# T17_Schematic_The_Useless_Box.net
KiCad netlist of a schematic drawn in EAGLE
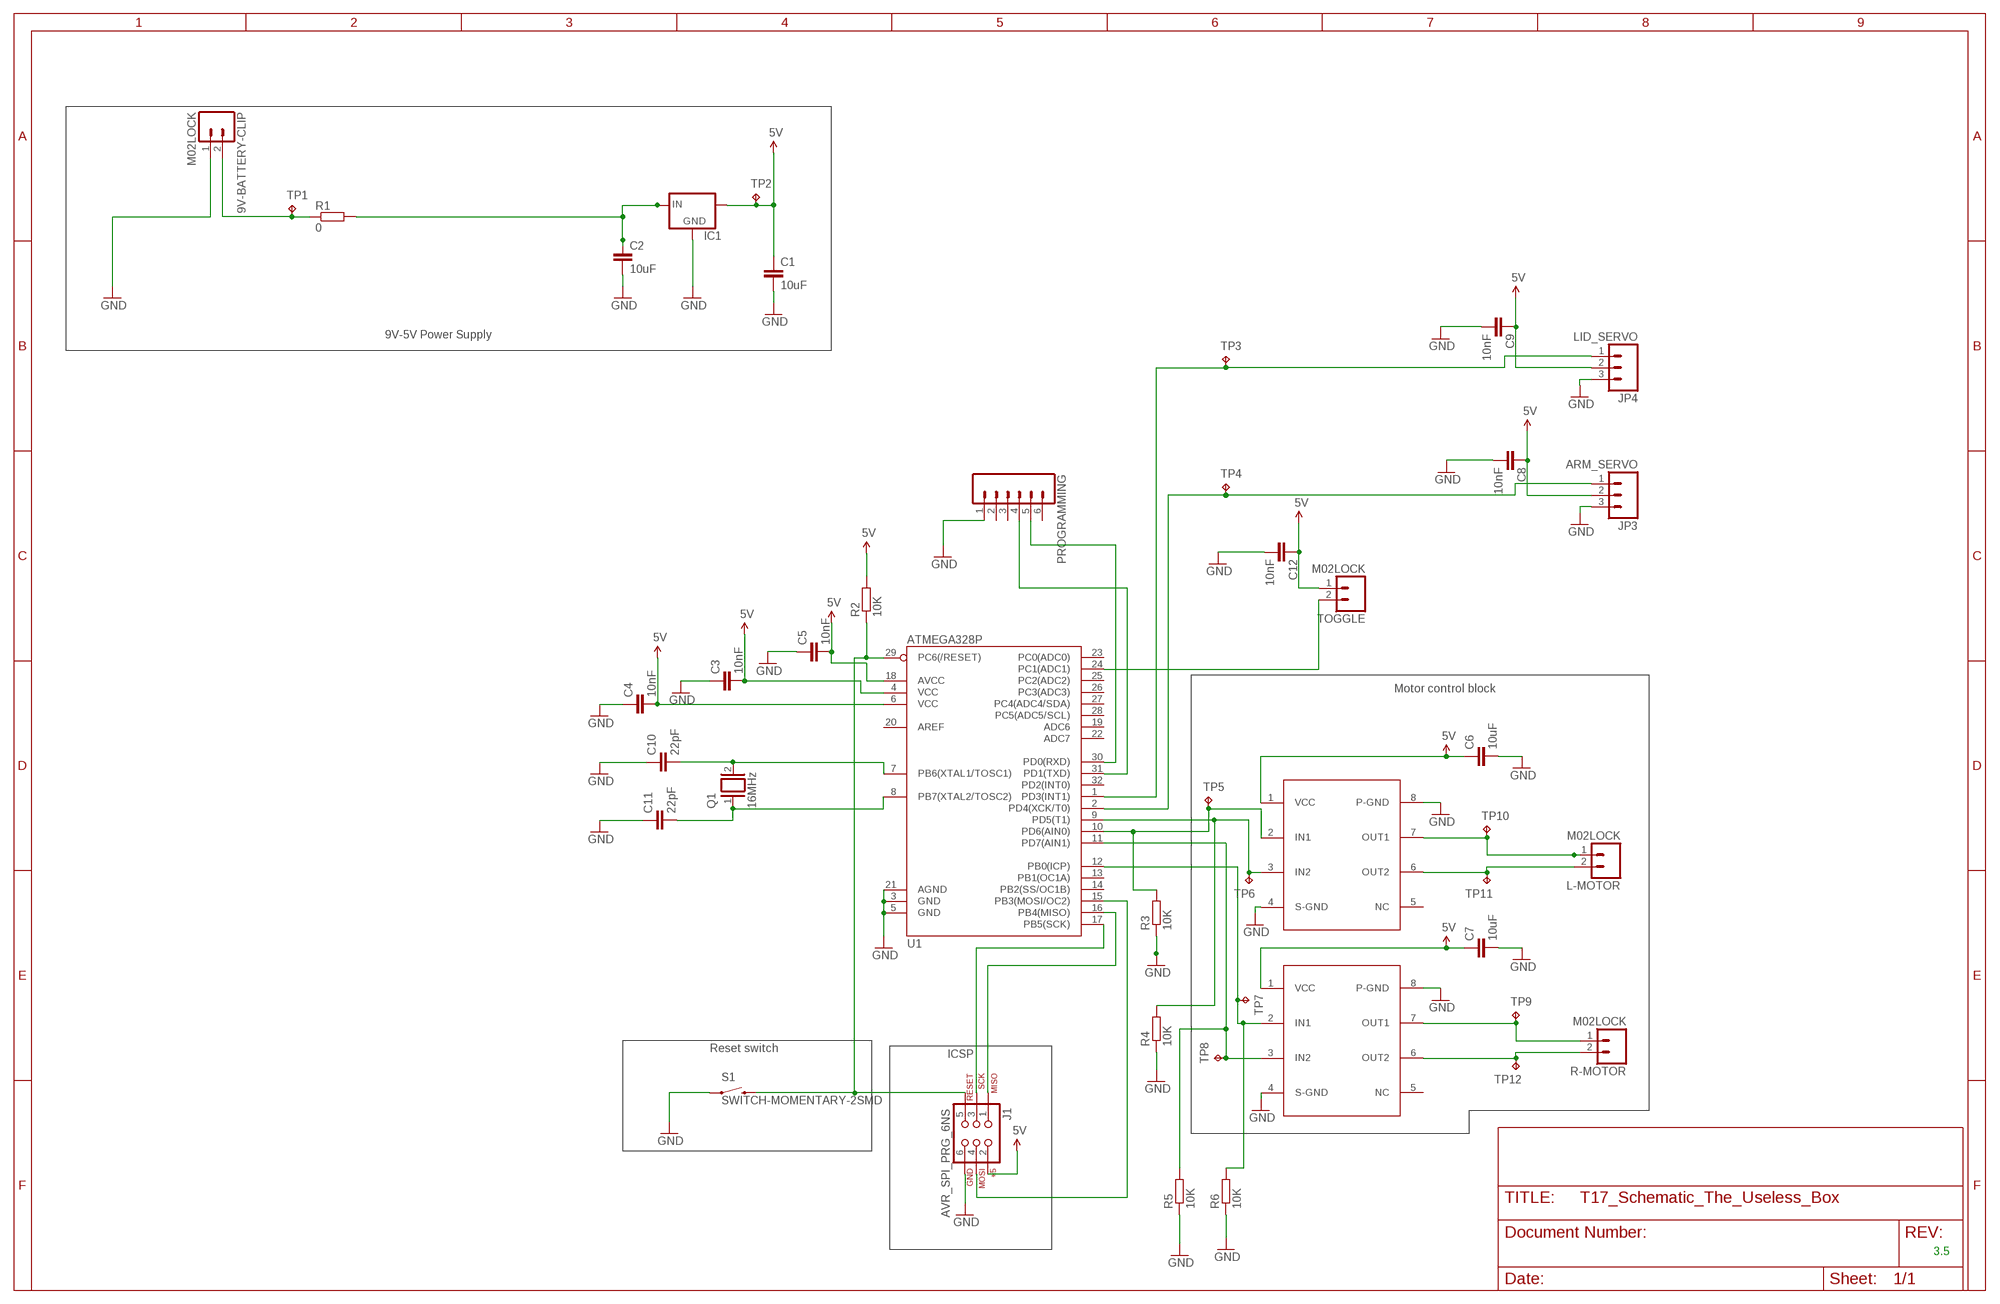
[diagram p0: schematic, sheet 1]

(export (version "E")
  (design (tool "Eeschema 10.0.6"))
  (components
    (comp (ref "9V-BATTERY-CLIP")
      (value "M02LOCK")
      (footprint "eagle-import:1X02_LOCK")
      (libsource (lib "eagle-import") (part "M02LOCK"))
    )
    (comp (ref "C1")
      (value "10uF")
      (footprint "eagle-import:C0805")
      (libsource (lib "eagle-import") (part "C-EUC0805"))
    )
    (comp (ref "C2")
      (value "10uF")
      (footprint "eagle-import:C0805")
      (libsource (lib "eagle-import") (part "C-EUC0805"))
    )
    (comp (ref "C3")
      (value "10nF")
      (footprint "eagle-import:C0805")
      (libsource (lib "eagle-import") (part "C-EUC0805"))
    )
    (comp (ref "C4")
      (value "10nF")
      (footprint "eagle-import:C0805")
      (libsource (lib "eagle-import") (part "C-EUC0805"))
    )
    (comp (ref "C5")
      (value "10nF")
      (footprint "eagle-import:C0805")
      (libsource (lib "eagle-import") (part "C-EUC0805"))
    )
    (comp (ref "C6")
      (value "10uF")
      (footprint "eagle-import:C0805")
      (libsource (lib "eagle-import") (part "C-EUC0805"))
    )
    (comp (ref "C7")
      (value "10uF")
      (footprint "eagle-import:C0805")
      (libsource (lib "eagle-import") (part "C-EUC0805"))
    )
    (comp (ref "C8")
      (value "10nF")
      (footprint "eagle-import:C0805")
      (libsource (lib "eagle-import") (part "C-EUC0805"))
    )
    (comp (ref "C9")
      (value "10nF")
      (footprint "eagle-import:C0805")
      (libsource (lib "eagle-import") (part "C-EUC0805"))
    )
    (comp (ref "C10")
      (value "22pF")
      (footprint "eagle-import:C0805")
      (libsource (lib "eagle-import") (part "C-EUC0805"))
    )
    (comp (ref "C11")
      (value "22pF")
      (footprint "eagle-import:C0805")
      (libsource (lib "eagle-import") (part "C-EUC0805"))
    )
    (comp (ref "C12")
      (value "10nF")
      (footprint "eagle-import:C0805")
      (libsource (lib "eagle-import") (part "C-EUC0805"))
    )
    (comp (ref "IC1")
      (value "V_REG_78XX-TO-220")
      (footprint "eagle-import:TO-220-ALT")
      (libsource (lib "eagle-import") (part "V_REG_78XX-TO-220"))
    )
    (comp (ref "J1")
      (value "AVR_SPI_PRG_6NS")
      (footprint "eagle-import:2X3-NS")
      (libsource (lib "eagle-import") (part "AVR_SPI_PRG_6NS"))
    )
    (comp (ref "JP3")
      (value "ARM_SERVO")
      (footprint "eagle-import:1X03")
      (libsource (lib "eagle-import") (part "M03PTH"))
    )
    (comp (ref "JP4")
      (value "LID_SERVO")
      (footprint "eagle-import:1X03")
      (libsource (lib "eagle-import") (part "M03PTH"))
    )
    (comp (ref "L-MOTOR")
      (value "M02LOCK")
      (footprint "eagle-import:1X02_LOCK")
      (libsource (lib "eagle-import") (part "M02LOCK"))
    )
    (comp (ref "PROGRAMMING")
      (value "M06NO_SILK_FEMALE_PTH")
      (footprint "eagle-import:1X06_NO_SILK")
      (libsource (lib "eagle-import") (part "M06NO_SILK_FEMALE_PTH"))
    )
    (comp (ref "Q1")
      (value "16MHz")
      (footprint "eagle-import:QS")
      (libsource (lib "eagle-import") (part "XTAL/S"))
    )
    (comp (ref "R-MOTOR")
      (value "M02LOCK")
      (footprint "eagle-import:1X02_LOCK")
      (libsource (lib "eagle-import") (part "M02LOCK"))
    )
    (comp (ref "R1")
      (value "0")
      (footprint "eagle-import:R0805")
      (libsource (lib "eagle-import") (part "R-EU_R0805"))
    )
    (comp (ref "R2")
      (value "10K")
      (footprint "eagle-import:R0805")
      (libsource (lib "eagle-import") (part "R-EU_R0805"))
    )
    (comp (ref "R3")
      (value "10K")
      (footprint "eagle-import:R0805")
      (libsource (lib "eagle-import") (part "R-EU_R0805"))
    )
    (comp (ref "R4")
      (value "10K")
      (footprint "eagle-import:R0805")
      (libsource (lib "eagle-import") (part "R-EU_R0805"))
    )
    (comp (ref "R5")
      (value "10K")
      (footprint "eagle-import:R0805")
      (libsource (lib "eagle-import") (part "R-EU_R0805"))
    )
    (comp (ref "R6")
      (value "10K")
      (footprint "eagle-import:R0805")
      (libsource (lib "eagle-import") (part "R-EU_R0805"))
    )
    (comp (ref "S1")
      (value "SWITCH-MOMENTARY-2SMD")
      (footprint "eagle-import:TACTILE-SWITCH-SMD")
      (libsource (lib "eagle-import") (part "SWITCH-MOMENTARY-2SMD"))
    )
    (comp (ref "TOGGLE")
      (value "M02LOCK")
      (footprint "eagle-import:1X02_LOCK")
      (libsource (lib "eagle-import") (part "M02LOCK"))
    )
    (comp (ref "TP1")
      (value "TPB1,27")
      (footprint "eagle-import:B1,27")
      (libsource (lib "eagle-import") (part "TPB1,27"))
    )
    (comp (ref "TP2")
      (value "TPB1,27")
      (footprint "eagle-import:B1,27")
      (libsource (lib "eagle-import") (part "TPB1,27"))
    )
    (comp (ref "TP3")
      (value "TPB1,27")
      (footprint "eagle-import:B1,27")
      (libsource (lib "eagle-import") (part "TPB1,27"))
    )
    (comp (ref "TP4")
      (value "TPB1,27")
      (footprint "eagle-import:B1,27")
      (libsource (lib "eagle-import") (part "TPB1,27"))
    )
    (comp (ref "TP5")
      (value "TPB1,27")
      (footprint "eagle-import:B1,27")
      (libsource (lib "eagle-import") (part "TPB1,27"))
    )
    (comp (ref "TP6")
      (value "TPB1,27")
      (footprint "eagle-import:B1,27")
      (libsource (lib "eagle-import") (part "TPB1,27"))
    )
    (comp (ref "TP7")
      (value "TPB1,27")
      (footprint "eagle-import:B1,27")
      (libsource (lib "eagle-import") (part "TPB1,27"))
    )
    (comp (ref "TP8")
      (value "TPB1,27")
      (footprint "eagle-import:B1,27")
      (libsource (lib "eagle-import") (part "TPB1,27"))
    )
    (comp (ref "TP9")
      (value "TPB1,27")
      (footprint "eagle-import:B1,27")
      (libsource (lib "eagle-import") (part "TPB1,27"))
    )
    (comp (ref "TP10")
      (value "TPB1,27")
      (footprint "eagle-import:B1,27")
      (libsource (lib "eagle-import") (part "TPB1,27"))
    )
    (comp (ref "TP11")
      (value "TPB1,27")
      (footprint "eagle-import:B1,27")
      (libsource (lib "eagle-import") (part "TPB1,27"))
    )
    (comp (ref "TP12")
      (value "TPB1,27")
      (footprint "eagle-import:B1,27")
      (libsource (lib "eagle-import") (part "TPB1,27"))
    )
    (comp (ref "U$1")
      (value "LB1938FA-AH")
      (footprint "eagle-import:MSOP8")
      (libsource (lib "eagle-import") (part "LB1938FA-AH"))
    )
    (comp (ref "U$2")
      (value "LB1938FA-AH")
      (footprint "eagle-import:MSOP8")
      (libsource (lib "eagle-import") (part "LB1938FA-AH"))
    )
    (comp (ref "U1")
      (value "ATMEGA328P")
      (footprint "eagle-import:TQFP32-08")
      (libsource (lib "eagle-import") (part "ATMEGA328_SMT"))
    )
  )
  (nets
    (net (code "1") (name "5V") (class "Default")
      (node (ref "C1") (pin "1") (pinfunction "1_1") (pintype "passive"))
      (node (ref "C12") (pin "1") (pinfunction "1_1") (pintype "passive"))
      (node (ref "C3") (pin "2") (pinfunction "2_2") (pintype "passive"))
      (node (ref "C4") (pin "2") (pinfunction "2_2") (pintype "passive"))
      (node (ref "C5") (pin "2") (pinfunction "2_2") (pintype "passive"))
      (node (ref "C6") (pin "1") (pinfunction "1_1") (pintype "passive"))
      (node (ref "C7") (pin "1") (pinfunction "1_1") (pintype "passive"))
      (node (ref "C8") (pin "1") (pinfunction "1_1") (pintype "passive"))
      (node (ref "C9") (pin "1") (pinfunction "1_1") (pintype "passive"))
      (node (ref "IC1") (pin "OUT") (pinfunction "OUT_OUT") (pintype "power_in"))
      (node (ref "J1") (pin "2") (pinfunction "2_2") (pintype "passive"))
      (node (ref "JP3") (pin "2") (pinfunction "2_2") (pintype "passive"))
      (node (ref "JP4") (pin "2") (pinfunction "2_2") (pintype "passive"))
      (node (ref "R2") (pin "2") (pinfunction "2_2") (pintype "passive"))
      (node (ref "TOGGLE") (pin "1") (pinfunction "1_1") (pintype "passive"))
      (node (ref "TP2") (pin "TP") (pinfunction "TP_TP") (pintype "input"))
      (node (ref "U$1") (pin "1") (pinfunction "VCC_1") (pintype "bidirectional"))
      (node (ref "U$2") (pin "1") (pinfunction "VCC_1") (pintype "bidirectional"))
      (node (ref "U1") (pin "18") (pinfunction "AVCC_18") (pintype "bidirectional"))
      (node (ref "U1") (pin "4") (pinfunction "VCC_4") (pintype "bidirectional"))
      (node (ref "U1") (pin "6") (pinfunction "VCC_6") (pintype "bidirectional"))
    )
    (net (code "2") (name "GND") (class "Default")
      (node (ref "9V-BATTERY-CLIP") (pin "1") (pinfunction "1_1") (pintype "passive"))
      (node (ref "C1") (pin "2") (pinfunction "2_2") (pintype "passive"))
      (node (ref "C10") (pin "1") (pinfunction "1_1") (pintype "passive"))
      (node (ref "C11") (pin "1") (pinfunction "1_1") (pintype "passive"))
      (node (ref "C12") (pin "2") (pinfunction "2_2") (pintype "passive"))
      (node (ref "C2") (pin "2") (pinfunction "2_2") (pintype "passive"))
      (node (ref "C3") (pin "1") (pinfunction "1_1") (pintype "passive"))
      (node (ref "C4") (pin "1") (pinfunction "1_1") (pintype "passive"))
      (node (ref "C5") (pin "1") (pinfunction "1_1") (pintype "passive"))
      (node (ref "C6") (pin "2") (pinfunction "2_2") (pintype "passive"))
      (node (ref "C7") (pin "2") (pinfunction "2_2") (pintype "passive"))
      (node (ref "C8") (pin "2") (pinfunction "2_2") (pintype "passive"))
      (node (ref "C9") (pin "2") (pinfunction "2_2") (pintype "passive"))
      (node (ref "IC1") (pin "GND") (pinfunction "GND_GND") (pintype "input"))
      (node (ref "J1") (pin "6") (pinfunction "6_6") (pintype "passive"))
      (node (ref "JP3") (pin "3") (pinfunction "3_3") (pintype "passive"))
      (node (ref "JP4") (pin "3") (pinfunction "3_3") (pintype "passive"))
      (node (ref "PROGRAMMING") (pin "1") (pinfunction "1_1") (pintype "passive"))
      (node (ref "R3") (pin "1") (pinfunction "1_1") (pintype "passive"))
      (node (ref "R4") (pin "1") (pinfunction "1_1") (pintype "passive"))
      (node (ref "R5") (pin "1") (pinfunction "1_1") (pintype "passive"))
      (node (ref "R6") (pin "1") (pinfunction "1_1") (pintype "passive"))
      (node (ref "S1") (pin "1") (pinfunction "1_1") (pintype "passive"))
      (node (ref "U$1") (pin "4") (pinfunction "S-GND_4") (pintype "bidirectional"))
      (node (ref "U$1") (pin "8") (pinfunction "P-GND_8") (pintype "bidirectional"))
      (node (ref "U$2") (pin "4") (pinfunction "S-GND_4") (pintype "bidirectional"))
      (node (ref "U$2") (pin "8") (pinfunction "P-GND_8") (pintype "bidirectional"))
      (node (ref "U1") (pin "21") (pinfunction "AGND_21") (pintype "bidirectional"))
      (node (ref "U1") (pin "3") (pinfunction "GND_3") (pintype "bidirectional"))
      (node (ref "U1") (pin "5") (pinfunction "GND_5") (pintype "bidirectional"))
    )
    (net (code "3") (name "Net-(9V-BATTERY-CLIP-Pad2)") (class "Default")
      (node (ref "9V-BATTERY-CLIP") (pin "2") (pinfunction "2_2") (pintype "passive"))
      (node (ref "R1") (pin "1") (pinfunction "1_1") (pintype "passive"))
      (node (ref "TP1") (pin "TP") (pinfunction "TP_TP") (pintype "input"))
    )
    (net (code "4") (name "Net-(C2-Pad1)") (class "Default")
      (node (ref "C2") (pin "1") (pinfunction "1_1") (pintype "passive"))
      (node (ref "IC1") (pin "IN") (pinfunction "IN_IN") (pintype "input"))
      (node (ref "R1") (pin "2") (pinfunction "2_2") (pintype "passive"))
    )
    (net (code "5") (name "Net-(S1-2)") (class "Default")
      (node (ref "J1") (pin "5") (pinfunction "5_5") (pintype "passive"))
      (node (ref "R2") (pin "1") (pinfunction "1_1") (pintype "passive"))
      (node (ref "S1") (pin "3") (pinfunction "2_3") (pintype "passive"))
      (node (ref "U1") (pin "29") (pinfunction "PC6(/RESET)_29") (pintype "bidirectional"))
    )
    (net (code "6") (name "Net-(U$1-IN1)") (class "Default")
      (node (ref "R6") (pin "2") (pinfunction "2_2") (pintype "passive"))
      (node (ref "TP7") (pin "TP") (pinfunction "TP_TP") (pintype "input"))
      (node (ref "U$1") (pin "2") (pinfunction "IN1_2") (pintype "bidirectional"))
      (node (ref "U1") (pin "12") (pinfunction "PB0(ICP)_12") (pintype "bidirectional"))
    )
    (net (code "7") (name "Net-(U$1-IN2)") (class "Default")
      (node (ref "R5") (pin "2") (pinfunction "2_2") (pintype "passive"))
      (node (ref "TP8") (pin "TP") (pinfunction "TP_TP") (pintype "input"))
      (node (ref "U$1") (pin "3") (pinfunction "IN2_3") (pintype "bidirectional"))
      (node (ref "U1") (pin "11") (pinfunction "PD7(AIN1)_11") (pintype "bidirectional"))
    )
    (net (code "8") (name "Net-(U$1-OUT1)") (class "Default")
      (node (ref "R-MOTOR") (pin "1") (pinfunction "1_1") (pintype "passive"))
      (node (ref "TP9") (pin "TP") (pinfunction "TP_TP") (pintype "input"))
      (node (ref "U$1") (pin "7") (pinfunction "OUT1_7") (pintype "bidirectional"))
    )
    (net (code "9") (name "Net-(U$1-OUT2)") (class "Default")
      (node (ref "R-MOTOR") (pin "2") (pinfunction "2_2") (pintype "passive"))
      (node (ref "TP12") (pin "TP") (pinfunction "TP_TP") (pintype "input"))
      (node (ref "U$1") (pin "6") (pinfunction "OUT2_6") (pintype "bidirectional"))
    )
    (net (code "10") (name "Net-(U$2-IN1)") (class "Default")
      (node (ref "R3") (pin "2") (pinfunction "2_2") (pintype "passive"))
      (node (ref "TP5") (pin "TP") (pinfunction "TP_TP") (pintype "input"))
      (node (ref "U$2") (pin "2") (pinfunction "IN1_2") (pintype "bidirectional"))
      (node (ref "U1") (pin "10") (pinfunction "PD6(AIN0)_10") (pintype "bidirectional"))
    )
    (net (code "11") (name "Net-(U$2-IN2)") (class "Default")
      (node (ref "R4") (pin "2") (pinfunction "2_2") (pintype "passive"))
      (node (ref "TP6") (pin "TP") (pinfunction "TP_TP") (pintype "input"))
      (node (ref "U$2") (pin "3") (pinfunction "IN2_3") (pintype "bidirectional"))
      (node (ref "U1") (pin "9") (pinfunction "PD5(T1)_9") (pintype "bidirectional"))
    )
    (net (code "12") (name "Net-(U$2-OUT1)") (class "Default")
      (node (ref "L-MOTOR") (pin "1") (pinfunction "1_1") (pintype "passive"))
      (node (ref "TP10") (pin "TP") (pinfunction "TP_TP") (pintype "input"))
      (node (ref "U$2") (pin "7") (pinfunction "OUT1_7") (pintype "bidirectional"))
    )
    (net (code "13") (name "Net-(U$2-OUT2)") (class "Default")
      (node (ref "L-MOTOR") (pin "2") (pinfunction "2_2") (pintype "passive"))
      (node (ref "TP11") (pin "TP") (pinfunction "TP_TP") (pintype "input"))
      (node (ref "U$2") (pin "6") (pinfunction "OUT2_6") (pintype "bidirectional"))
    )
    (net (code "14") (name "Net-(U1-PB3(MOSI{slash}OC2))") (class "Default")
      (node (ref "J1") (pin "4") (pinfunction "4_4") (pintype "passive"))
      (node (ref "U1") (pin "15") (pinfunction "PB3(MOSI/OC2)_15") (pintype "bidirectional"))
    )
    (net (code "15") (name "Net-(U1-PB4(MISO))") (class "Default")
      (node (ref "J1") (pin "1") (pinfunction "1_1") (pintype "passive"))
      (node (ref "U1") (pin "16") (pinfunction "PB4(MISO)_16") (pintype "bidirectional"))
    )
    (net (code "16") (name "Net-(U1-PB5(SCK))") (class "Default")
      (node (ref "J1") (pin "3") (pinfunction "3_3") (pintype "passive"))
      (node (ref "U1") (pin "17") (pinfunction "PB5(SCK)_17") (pintype "bidirectional"))
    )
    (net (code "17") (name "Net-(U1-PB6(XTAL1{slash}TOSC1))") (class "Default")
      (node (ref "C10") (pin "2") (pinfunction "2_2") (pintype "passive"))
      (node (ref "Q1") (pin "2") (pinfunction "2_2") (pintype "passive"))
      (node (ref "U1") (pin "7") (pinfunction "PB6(XTAL1/TOSC1)_7") (pintype "bidirectional"))
    )
    (net (code "18") (name "Net-(U1-PB7(XTAL2{slash}TOSC2))") (class "Default")
      (node (ref "C11") (pin "2") (pinfunction "2_2") (pintype "passive"))
      (node (ref "Q1") (pin "1") (pinfunction "1_1") (pintype "passive"))
      (node (ref "U1") (pin "8") (pinfunction "PB7(XTAL2/TOSC2)_8") (pintype "bidirectional"))
    )
    (net (code "19") (name "Net-(U1-PC1(ADC1))") (class "Default")
      (node (ref "TOGGLE") (pin "2") (pinfunction "2_2") (pintype "passive"))
      (node (ref "U1") (pin "24") (pinfunction "PC1(ADC1)_24") (pintype "bidirectional"))
    )
    (net (code "20") (name "Net-(U1-PD0(RXD))") (class "Default")
      (node (ref "PROGRAMMING") (pin "5") (pinfunction "5_5") (pintype "passive"))
      (node (ref "U1") (pin "30") (pinfunction "PD0(RXD)_30") (pintype "bidirectional"))
    )
    (net (code "21") (name "Net-(U1-PD1(TXD))") (class "Default")
      (node (ref "PROGRAMMING") (pin "4") (pinfunction "4_4") (pintype "passive"))
      (node (ref "U1") (pin "31") (pinfunction "PD1(TXD)_31") (pintype "bidirectional"))
    )
    (net (code "22") (name "Net-(U1-PD3(INT1))") (class "Default")
      (node (ref "JP4") (pin "1") (pinfunction "1_1") (pintype "passive"))
      (node (ref "TP3") (pin "TP") (pinfunction "TP_TP") (pintype "input"))
      (node (ref "U1") (pin "1") (pinfunction "PD3(INT1)_1") (pintype "bidirectional"))
    )
    (net (code "23") (name "Net-(U1-PD4(XCK{slash}T0))") (class "Default")
      (node (ref "JP3") (pin "1") (pinfunction "1_1") (pintype "passive"))
      (node (ref "TP4") (pin "TP") (pinfunction "TP_TP") (pintype "input"))
      (node (ref "U1") (pin "2") (pinfunction "PD4(XCK/T0)_2") (pintype "bidirectional"))
    )
    (net (code "24") (name "unconnected-(PROGRAMMING-Pad2)") (class "Default")
      (node (ref "PROGRAMMING") (pin "2") (pinfunction "2_2") (pintype "passive"))
    )
    (net (code "25") (name "unconnected-(PROGRAMMING-Pad3)") (class "Default")
      (node (ref "PROGRAMMING") (pin "3") (pinfunction "3_3") (pintype "passive"))
    )
    (net (code "26") (name "unconnected-(PROGRAMMING-Pad6)") (class "Default")
      (node (ref "PROGRAMMING") (pin "6") (pinfunction "6_6") (pintype "passive"))
    )
    (net (code "27") (name "unconnected-(U$1-NC-Pad5)") (class "Default")
      (node (ref "U$1") (pin "5") (pinfunction "NC_5") (pintype "bidirectional"))
    )
    (net (code "28") (name "unconnected-(U$2-NC-Pad5)") (class "Default")
      (node (ref "U$2") (pin "5") (pinfunction "NC_5") (pintype "bidirectional"))
    )
    (net (code "29") (name "unconnected-(U1-ADC6-Pad19)") (class "Default")
      (node (ref "U1") (pin "19") (pinfunction "ADC6_19") (pintype "bidirectional"))
    )
    (net (code "30") (name "unconnected-(U1-ADC7-Pad22)") (class "Default")
      (node (ref "U1") (pin "22") (pinfunction "ADC7_22") (pintype "bidirectional"))
    )
    (net (code "31") (name "unconnected-(U1-AREF-Pad20)") (class "Default")
      (node (ref "U1") (pin "20") (pinfunction "AREF_20") (pintype "bidirectional"))
    )
    (net (code "32") (name "unconnected-(U1-PB1(OC1A)-Pad13)") (class "Default")
      (node (ref "U1") (pin "13") (pinfunction "PB1(OC1A)_13") (pintype "bidirectional"))
    )
    (net (code "33") (name "unconnected-(U1-PB2(SS{slash}OC1B)-Pad14)") (class "Default")
      (node (ref "U1") (pin "14") (pinfunction "PB2(SS/OC1B)_14") (pintype "bidirectional"))
    )
    (net (code "34") (name "unconnected-(U1-PC0(ADC0)-Pad23)") (class "Default")
      (node (ref "U1") (pin "23") (pinfunction "PC0(ADC0)_23") (pintype "bidirectional"))
    )
    (net (code "35") (name "unconnected-(U1-PC2(ADC2)-Pad25)") (class "Default")
      (node (ref "U1") (pin "25") (pinfunction "PC2(ADC2)_25") (pintype "bidirectional"))
    )
    (net (code "36") (name "unconnected-(U1-PC3(ADC3)-Pad26)") (class "Default")
      (node (ref "U1") (pin "26") (pinfunction "PC3(ADC3)_26") (pintype "bidirectional"))
    )
    (net (code "37") (name "unconnected-(U1-PC4(ADC4{slash}SDA)-Pad27)") (class "Default")
      (node (ref "U1") (pin "27") (pinfunction "PC4(ADC4/SDA)_27") (pintype "bidirectional"))
    )
    (net (code "38") (name "unconnected-(U1-PC5(ADC5{slash}SCL)-Pad28)") (class "Default")
      (node (ref "U1") (pin "28") (pinfunction "PC5(ADC5/SCL)_28") (pintype "bidirectional"))
    )
    (net (code "39") (name "unconnected-(U1-PD2(INT0)-Pad32)") (class "Default")
      (node (ref "U1") (pin "32") (pinfunction "PD2(INT0)_32") (pintype "bidirectional"))
    )
  )
)
